# detector00.net
KiCad netlist of a schematic drawn in EAGLE
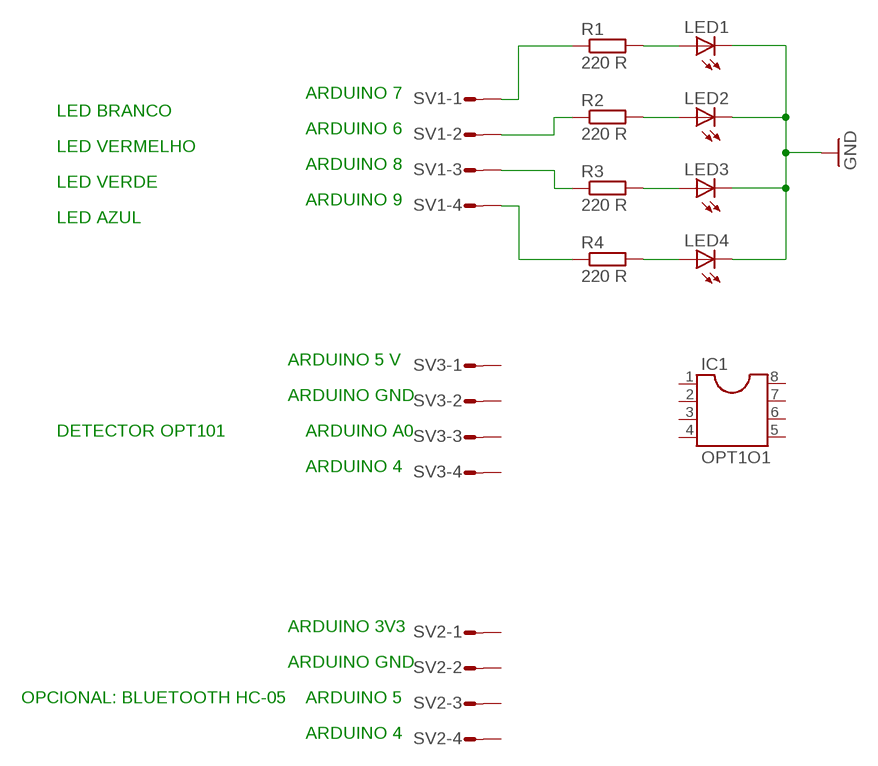
[diagram p0: schematic, sheet 1]

(export (version "E")
  (design (tool "Eeschema 10.0.6"))
  (components
    (comp (ref "IC1")
      (value "OPT1O1")
      (footprint "eagle-import:DIL08")
      (libsource (lib "eagle-import") (part "DIL8"))
    )
    (comp (ref "LED1")
      (value "LED5MM")
      (footprint "eagle-import:LED5MM")
      (libsource (lib "eagle-import") (part "LED5MM"))
    )
    (comp (ref "LED2")
      (value "LED5MM")
      (footprint "eagle-import:LED5MM")
      (libsource (lib "eagle-import") (part "LED5MM"))
    )
    (comp (ref "LED3")
      (value "LED5MM")
      (footprint "eagle-import:LED5MM")
      (libsource (lib "eagle-import") (part "LED5MM"))
    )
    (comp (ref "LED4")
      (value "LED5MM")
      (footprint "eagle-import:LED5MM")
      (libsource (lib "eagle-import") (part "LED5MM"))
    )
    (comp (ref "R1")
      (value "220 R")
      (footprint "eagle-import:0204_7")
      (libsource (lib "eagle-import") (part "R-EU_0204/7"))
    )
    (comp (ref "R2")
      (value "220 R")
      (footprint "eagle-import:0204_7")
      (libsource (lib "eagle-import") (part "R-EU_0204/7"))
    )
    (comp (ref "R3")
      (value "220 R")
      (footprint "eagle-import:0204_7")
      (libsource (lib "eagle-import") (part "R-EU_0204/7"))
    )
    (comp (ref "R4")
      (value "220 R")
      (footprint "eagle-import:0204_7")
      (libsource (lib "eagle-import") (part "R-EU_0204/7"))
    )
    (comp (ref "SV1")
      (value "L04P")
      (footprint "eagle-import:L04P")
      (libsource (lib "eagle-import") (part "L04P"))
    )
    (comp (ref "SV2")
      (value "L04P")
      (footprint "eagle-import:L04P")
      (libsource (lib "eagle-import") (part "L04P"))
    )
    (comp (ref "SV3")
      (value "L04P")
      (footprint "eagle-import:L04P")
      (libsource (lib "eagle-import") (part "L04P"))
    )
  )
  (nets
    (net (code "1") (name "GND") (class "Default")
      (node (ref "LED1") (pin "K") (pinfunction "C_K") (pintype "passive"))
      (node (ref "LED2") (pin "K") (pinfunction "C_K") (pintype "passive"))
      (node (ref "LED3") (pin "K") (pinfunction "C_K") (pintype "passive"))
      (node (ref "LED4") (pin "K") (pinfunction "C_K") (pintype "passive"))
    )
    (net (code "2") (name "Net-(LED1-PadA)") (class "Default")
      (node (ref "LED1") (pin "A") (pinfunction "A_A") (pintype "passive"))
      (node (ref "R1") (pin "2") (pinfunction "2_2") (pintype "passive"))
    )
    (net (code "3") (name "Net-(LED2-PadA)") (class "Default")
      (node (ref "LED2") (pin "A") (pinfunction "A_A") (pintype "passive"))
      (node (ref "R2") (pin "2") (pinfunction "2_2") (pintype "passive"))
    )
    (net (code "4") (name "Net-(LED3-PadA)") (class "Default")
      (node (ref "LED3") (pin "A") (pinfunction "A_A") (pintype "passive"))
      (node (ref "R3") (pin "2") (pinfunction "2_2") (pintype "passive"))
    )
    (net (code "5") (name "Net-(LED4-PadA)") (class "Default")
      (node (ref "LED4") (pin "A") (pinfunction "A_A") (pintype "passive"))
      (node (ref "R4") (pin "2") (pinfunction "2_2") (pintype "passive"))
    )
    (net (code "6") (name "Net-(SV1A-S)") (class "Default")
      (node (ref "R1") (pin "1") (pinfunction "1_1") (pintype "passive"))
      (node (ref "SV1") (pin "1") (pinfunction "S_1") (pintype "passive"))
    )
    (net (code "7") (name "Net-(SV1B-S)") (class "Default")
      (node (ref "R2") (pin "1") (pinfunction "1_1") (pintype "passive"))
      (node (ref "SV1") (pin "2") (pinfunction "S_2") (pintype "passive"))
    )
    (net (code "8") (name "Net-(SV1C-S)") (class "Default")
      (node (ref "R3") (pin "1") (pinfunction "1_1") (pintype "passive"))
      (node (ref "SV1") (pin "3") (pinfunction "S_3") (pintype "passive"))
    )
    (net (code "9") (name "Net-(SV1D-S)") (class "Default")
      (node (ref "R4") (pin "1") (pinfunction "1_1") (pintype "passive"))
      (node (ref "SV1") (pin "4") (pinfunction "S_4") (pintype "passive"))
    )
    (net (code "10") (name "unconnected-(IC1-Pad1)") (class "Default")
      (node (ref "IC1") (pin "1") (pinfunction "1_1") (pintype "passive"))
    )
    (net (code "11") (name "unconnected-(IC1-Pad2)") (class "Default")
      (node (ref "IC1") (pin "2") (pinfunction "2_2") (pintype "passive"))
    )
    (net (code "12") (name "unconnected-(IC1-Pad3)") (class "Default")
      (node (ref "IC1") (pin "3") (pinfunction "3_3") (pintype "passive"))
    )
    (net (code "13") (name "unconnected-(IC1-Pad4)") (class "Default")
      (node (ref "IC1") (pin "4") (pinfunction "4_4") (pintype "passive"))
    )
    (net (code "14") (name "unconnected-(IC1-Pad5)") (class "Default")
      (node (ref "IC1") (pin "5") (pinfunction "5_5") (pintype "passive"))
    )
    (net (code "15") (name "unconnected-(IC1-Pad6)") (class "Default")
      (node (ref "IC1") (pin "6") (pinfunction "6_6") (pintype "passive"))
    )
    (net (code "16") (name "unconnected-(IC1-Pad7)") (class "Default")
      (node (ref "IC1") (pin "7") (pinfunction "7_7") (pintype "passive"))
    )
    (net (code "17") (name "unconnected-(IC1-Pad8)") (class "Default")
      (node (ref "IC1") (pin "8") (pinfunction "8_8") (pintype "passive"))
    )
    (net (code "18") (name "unconnected-(SV2A-S-Pad1)") (class "Default")
      (node (ref "SV2") (pin "1") (pinfunction "S_1") (pintype "passive"))
    )
    (net (code "19") (name "unconnected-(SV2B-S-Pad2)") (class "Default")
      (node (ref "SV2") (pin "2") (pinfunction "S_2") (pintype "passive"))
    )
    (net (code "20") (name "unconnected-(SV2C-S-Pad3)") (class "Default")
      (node (ref "SV2") (pin "3") (pinfunction "S_3") (pintype "passive"))
    )
    (net (code "21") (name "unconnected-(SV2D-S-Pad4)") (class "Default")
      (node (ref "SV2") (pin "4") (pinfunction "S_4") (pintype "passive"))
    )
    (net (code "22") (name "unconnected-(SV3A-S-Pad1)") (class "Default")
      (node (ref "SV3") (pin "1") (pinfunction "S_1") (pintype "passive"))
    )
    (net (code "23") (name "unconnected-(SV3B-S-Pad2)") (class "Default")
      (node (ref "SV3") (pin "2") (pinfunction "S_2") (pintype "passive"))
    )
    (net (code "24") (name "unconnected-(SV3C-S-Pad3)") (class "Default")
      (node (ref "SV3") (pin "3") (pinfunction "S_3") (pintype "passive"))
    )
    (net (code "25") (name "unconnected-(SV3D-S-Pad4)") (class "Default")
      (node (ref "SV3") (pin "4") (pinfunction "S_4") (pintype "passive"))
    )
  )
)
